# Sheet.net
KiCad netlist of a schematic drawn in Altium Designer
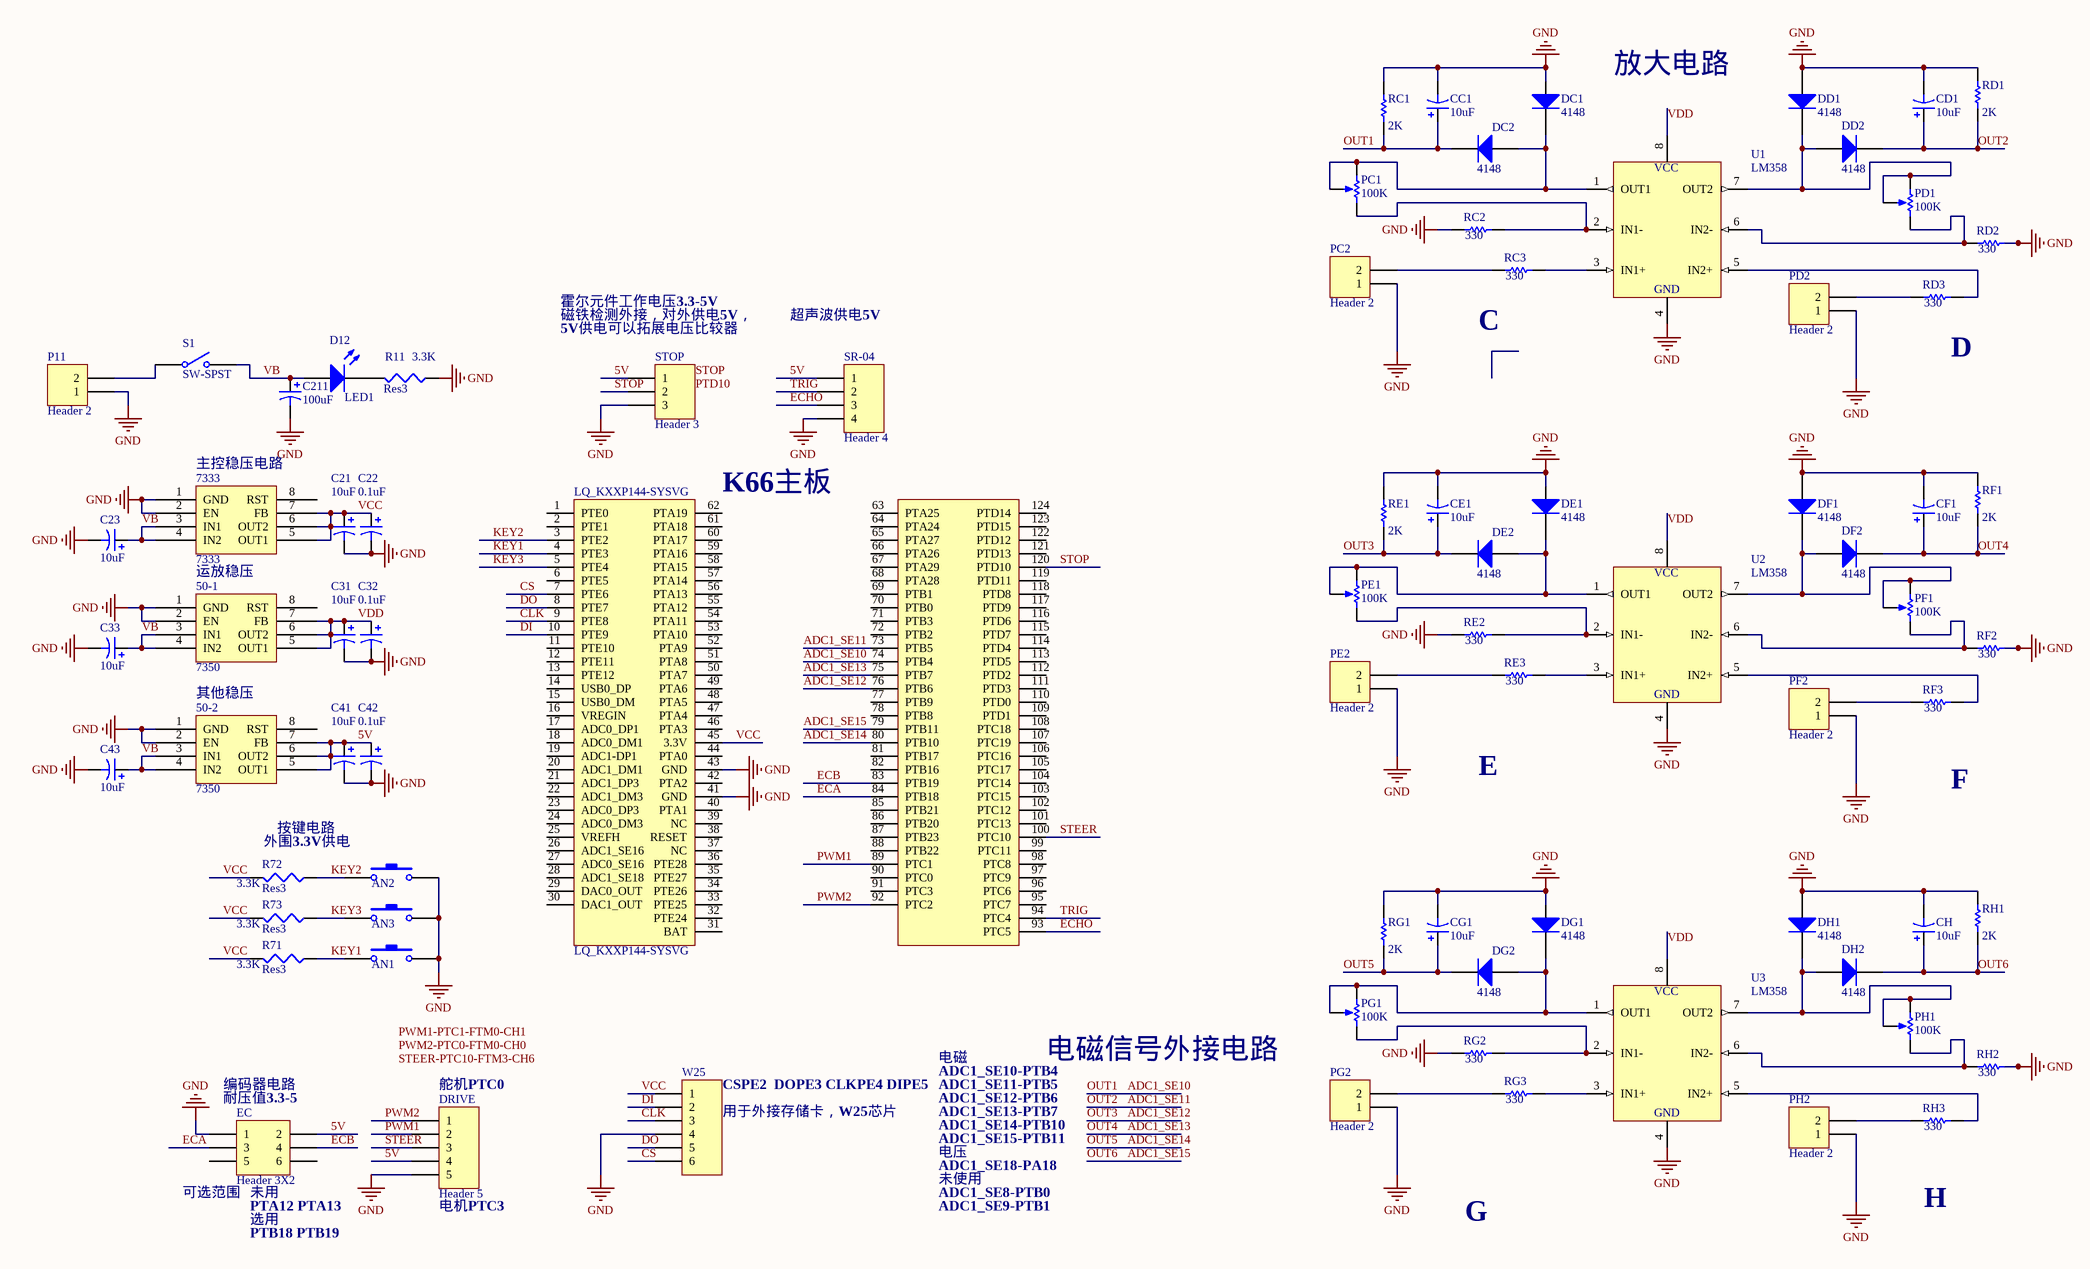
[diagram p0: Sheet.SchDoc]

(export (version "E")
  (design (tool "Eeschema 10.0.6"))
  (components
    (comp (ref "50-1") (value "7350") (footprint "SOP8_N") (libsource (lib "vehicle") (part "7350")))
    (comp (ref "50-2") (value "7350") (footprint "SOP8_N") (libsource (lib "vehicle") (part "7350")))
    (comp (ref "7333") (value "7333") (footprint "SO8_N") (libsource (lib "vehicle") (part "7333")))
    (comp (ref "AN1")
      (value "Button")
      (footprint "SMT4*6*2.5")
      (fields (field (name "PUBLISHER") "Altium Limited"))
      (libsource (lib "开关按键器件") (part "Button"))
    )
    (comp (ref "AN2")
      (value "Button")
      (footprint "SMT4*6*2.5")
      (fields (field (name "PUBLISHER") "Altium Limited"))
      (libsource (lib "开关按键器件") (part "Button"))
    )
    (comp (ref "AN3")
      (value "Button")
      (footprint "SMT4*6*2.5")
      (fields (field (name "PUBLISHER") "Altium Limited"))
      (libsource (lib "开关按键器件") (part "Button"))
    )
    (comp (ref "C21")
      (value "10uF")
      (footprint "C6032")
      (description "Polarized Capacitor (Surface Mount)")
      (fields (field (name "Comment") "Cap Pol3") (field (name "PUBLISHER") "Altium Limited"))
      (libsource (lib "Miscellaneous Devices") (part "Cap Pol3"))
    )
    (comp (ref "C22")
      (value "0.1uF")
      (footprint "C3216")
      (description "Polarized Capacitor (Surface Mount)")
      (fields (field (name "Comment") "Cap Pol3") (field (name "PUBLISHER") "Altium Limited"))
      (libsource (lib "Miscellaneous Devices") (part "Cap Pol3"))
    )
    (comp (ref "C23")
      (value "10uF")
      (footprint "C6032")
      (description "Polarized Capacitor (Surface Mount)")
      (fields (field (name "Comment") "Cap Pol3") (field (name "PUBLISHER") "Altium Limited"))
      (libsource (lib "Miscellaneous Devices") (part "Cap Pol3"))
    )
    (comp (ref "C31")
      (value "10uF")
      (footprint "C6032")
      (description "Polarized Capacitor (Surface Mount)")
      (fields (field (name "Comment") "Cap Pol3") (field (name "PUBLISHER") "Altium Limited"))
      (libsource (lib "Miscellaneous Devices") (part "Cap Pol3"))
    )
    (comp (ref "C32")
      (value "0.1uF")
      (footprint "C3216")
      (description "Polarized Capacitor (Surface Mount)")
      (fields (field (name "Comment") "Cap Pol3") (field (name "PUBLISHER") "Altium Limited"))
      (libsource (lib "Miscellaneous Devices") (part "Cap Pol3"))
    )
    (comp (ref "C33")
      (value "10uF")
      (footprint "C6032")
      (description "Polarized Capacitor (Surface Mount)")
      (fields (field (name "Comment") "Cap Pol3") (field (name "PUBLISHER") "Altium Limited"))
      (libsource (lib "Miscellaneous Devices") (part "Cap Pol3"))
    )
    (comp (ref "C41")
      (value "10uF")
      (footprint "C6032")
      (description "Polarized Capacitor (Surface Mount)")
      (fields (field (name "Comment") "Cap Pol3") (field (name "PUBLISHER") "Altium Limited"))
      (libsource (lib "Miscellaneous Devices") (part "Cap Pol3"))
    )
    (comp (ref "C42")
      (value "0.1uF")
      (footprint "C3216")
      (description "Polarized Capacitor (Surface Mount)")
      (fields (field (name "Comment") "Cap Pol3") (field (name "PUBLISHER") "Altium Limited"))
      (libsource (lib "Miscellaneous Devices") (part "Cap Pol3"))
    )
    (comp (ref "C43")
      (value "10uF")
      (footprint "C6032")
      (description "Polarized Capacitor (Surface Mount)")
      (fields (field (name "Comment") "Cap Pol3") (field (name "PUBLISHER") "Altium Limited"))
      (libsource (lib "Miscellaneous Devices") (part "Cap Pol3"))
    )
    (comp (ref "C211")
      (value "100uF")
      (footprint "C7343")
      (description "Polarized Capacitor (Surface Mount)")
      (fields (field (name "Comment") "Cap Pol3") (field (name "PUBLISHER") "Altium Limited"))
      (libsource (lib "Miscellaneous Devices") (part "Cap Pol3"))
    )
    (comp (ref "CC1")
      (value "10uF")
      (footprint "C6032")
      (description "Polarized Capacitor (Surface Mount)")
      (fields (field (name "Comment") "Cap Pol3") (field (name "PUBLISHER") "Altium Limited"))
      (libsource (lib "Miscellaneous Devices") (part "Cap Pol3"))
    )
    (comp (ref "CD1")
      (value "10uF")
      (footprint "C6032")
      (description "Polarized Capacitor (Surface Mount)")
      (fields (field (name "Comment") "Cap Pol3") (field (name "PUBLISHER") "Altium Limited"))
      (libsource (lib "Miscellaneous Devices") (part "Cap Pol3"))
    )
    (comp (ref "CE1")
      (value "10uF")
      (footprint "C6032")
      (description "Polarized Capacitor (Surface Mount)")
      (fields (field (name "Comment") "Cap Pol3") (field (name "PUBLISHER") "Altium Limited"))
      (libsource (lib "Miscellaneous Devices") (part "Cap Pol3"))
    )
    (comp (ref "CF1")
      (value "10uF")
      (footprint "C6032")
      (description "Polarized Capacitor (Surface Mount)")
      (fields (field (name "Comment") "Cap Pol3") (field (name "PUBLISHER") "Altium Limited"))
      (libsource (lib "Miscellaneous Devices") (part "Cap Pol3"))
    )
    (comp (ref "CG1")
      (value "10uF")
      (footprint "C6032")
      (description "Polarized Capacitor (Surface Mount)")
      (fields (field (name "Comment") "Cap Pol3") (field (name "PUBLISHER") "Altium Limited"))
      (libsource (lib "Miscellaneous Devices") (part "Cap Pol3"))
    )
    (comp (ref "CH")
      (value "10uF")
      (footprint "C6032")
      (description "Polarized Capacitor (Surface Mount)")
      (fields (field (name "Comment") "Cap Pol3") (field (name "PUBLISHER") "Altium Limited"))
      (libsource (lib "Miscellaneous Devices") (part "Cap Pol3"))
    )
    (comp (ref "D12")
      (value "LED1")
      (footprint "SMA")
      (description "Typical BLUE SiC LED")
      (fields (field (name "PUBLISHER") "Altium Limited"))
      (libsource (lib "Miscellaneous Devices") (part "LED3"))
    )
    (comp (ref "DC1")
      (value "4148")
      (footprint "SMA")
      (description "Default Diode")
      (fields (field (name "PUBLISHER") "Altium Limited"))
      (libsource (lib "Miscellaneous Devices") (part "Diode"))
    )
    (comp (ref "DC2")
      (value "4148")
      (footprint "SMA")
      (description "Default Diode")
      (fields (field (name "PUBLISHER") "Altium Limited"))
      (libsource (lib "Miscellaneous Devices") (part "Diode"))
    )
    (comp (ref "DD1")
      (value "4148")
      (footprint "SMA")
      (description "Default Diode")
      (fields (field (name "PUBLISHER") "Altium Limited"))
      (libsource (lib "Miscellaneous Devices") (part "Diode"))
    )
    (comp (ref "DD2")
      (value "4148")
      (footprint "SMA")
      (description "Default Diode")
      (fields (field (name "PUBLISHER") "Altium Limited"))
      (libsource (lib "Miscellaneous Devices") (part "Diode"))
    )
    (comp (ref "DE1")
      (value "4148")
      (footprint "SMA")
      (description "Default Diode")
      (fields (field (name "PUBLISHER") "Altium Limited"))
      (libsource (lib "Miscellaneous Devices") (part "Diode"))
    )
    (comp (ref "DE2")
      (value "4148")
      (footprint "SMA")
      (description "Default Diode")
      (fields (field (name "PUBLISHER") "Altium Limited"))
      (libsource (lib "Miscellaneous Devices") (part "Diode"))
    )
    (comp (ref "DF1")
      (value "4148")
      (footprint "SMA")
      (description "Default Diode")
      (fields (field (name "PUBLISHER") "Altium Limited"))
      (libsource (lib "Miscellaneous Devices") (part "Diode"))
    )
    (comp (ref "DF2")
      (value "4148")
      (footprint "SMA")
      (description "Default Diode")
      (fields (field (name "PUBLISHER") "Altium Limited"))
      (libsource (lib "Miscellaneous Devices") (part "Diode"))
    )
    (comp (ref "DG1")
      (value "4148")
      (footprint "SMA")
      (description "Default Diode")
      (fields (field (name "PUBLISHER") "Altium Limited"))
      (libsource (lib "Miscellaneous Devices") (part "Diode"))
    )
    (comp (ref "DG2")
      (value "4148")
      (footprint "SMA")
      (description "Default Diode")
      (fields (field (name "PUBLISHER") "Altium Limited"))
      (libsource (lib "Miscellaneous Devices") (part "Diode"))
    )
    (comp (ref "DH1")
      (value "4148")
      (footprint "SMA")
      (description "Default Diode")
      (fields (field (name "PUBLISHER") "Altium Limited"))
      (libsource (lib "Miscellaneous Devices") (part "Diode"))
    )
    (comp (ref "DH2")
      (value "4148")
      (footprint "SMA")
      (description "Default Diode")
      (fields (field (name "PUBLISHER") "Altium Limited"))
      (libsource (lib "Miscellaneous Devices") (part "Diode"))
    )
    (comp (ref "DRIVE")
      (value "Header 5")
      (footprint "HX2.54-5")
      (description "Header, 5-Pin")
      (fields (field (name "PUBLISHER") "Altium Limited"))
      (libsource (lib "连接器") (part "Header 5"))
    )
    (comp (ref "EC")
      (value "Header 3X2")
      (footprint "HDR2X3")
      (description "Header, 3-Pin, Dual row")
      (fields (field (name "PUBLISHER") "Altium Limited"))
      (libsource (lib "连接器") (part "Header 3X2"))
    )
    (comp (ref "LQ_KXXP144-SYSVG")
      (value "LQ_KXXP144-SYSVG")
      (footprint "LQ_KXXP144-SYSVG")
      (libsource (lib "LQ_KXXP144-SYSVGSCH") (part "LQ_KXXP144-SYSVG"))
    )
    (comp (ref "P11")
      (value "Header 2")
      (footprint "2PIN-5.08B")
      (description "Header, 2-Pin")
      (fields (field (name "PUBLISHER") "Altium Limited"))
      (libsource (lib "Miscellaneous Connectors") (part "Header 2"))
    )
    (comp (ref "PC1")
      (value "100K")
      (footprint "VR_B1")
      (description "精密可调电阻")
      (fields (field (name "Comment") "RPot") (field (name "PUBLISHER") "Altium Limited"))
      (libsource (lib "32mini") (part "RPot"))
    )
    (comp (ref "PC2")
      (value "Header 2")
      (footprint "HX2.54-2")
      (description "Header, 2-Pin")
      (fields (field (name "PUBLISHER") "Altium Limited"))
      (libsource (lib "Miscellaneous Connectors") (part "Header 2"))
    )
    (comp (ref "PD1")
      (value "100K")
      (footprint "VR_B1")
      (description "精密可调电阻")
      (fields (field (name "Comment") "RPot") (field (name "PUBLISHER") "Altium Limited"))
      (libsource (lib "32mini") (part "RPot"))
    )
    (comp (ref "PD2")
      (value "Header 2")
      (footprint "HX2.54-2")
      (description "Header, 2-Pin")
      (fields (field (name "PUBLISHER") "Altium Limited"))
      (libsource (lib "Miscellaneous Connectors") (part "Header 2"))
    )
    (comp (ref "PE1")
      (value "100K")
      (footprint "VR_B1")
      (description "精密可调电阻")
      (fields (field (name "Comment") "RPot") (field (name "PUBLISHER") "Altium Limited"))
      (libsource (lib "32mini") (part "RPot"))
    )
    (comp (ref "PE2")
      (value "Header 2")
      (footprint "HX2.54-2")
      (description "Header, 2-Pin")
      (fields (field (name "PUBLISHER") "Altium Limited"))
      (libsource (lib "Miscellaneous Connectors") (part "Header 2"))
    )
    (comp (ref "PF1")
      (value "100K")
      (footprint "VR_B1")
      (description "精密可调电阻")
      (fields (field (name "Comment") "RPot") (field (name "PUBLISHER") "Altium Limited"))
      (libsource (lib "32mini") (part "RPot"))
    )
    (comp (ref "PF2")
      (value "Header 2")
      (footprint "HX2.54-2")
      (description "Header, 2-Pin")
      (fields (field (name "PUBLISHER") "Altium Limited"))
      (libsource (lib "Miscellaneous Connectors") (part "Header 2"))
    )
    (comp (ref "PG1")
      (value "100K")
      (footprint "VR_B1")
      (description "精密可调电阻")
      (fields (field (name "Comment") "RPot") (field (name "PUBLISHER") "Altium Limited"))
      (libsource (lib "32mini") (part "RPot"))
    )
    (comp (ref "PG2")
      (value "Header 2")
      (footprint "HX2.54-2")
      (description "Header, 2-Pin")
      (fields (field (name "PUBLISHER") "Altium Limited"))
      (libsource (lib "Miscellaneous Connectors") (part "Header 2"))
    )
    (comp (ref "PH1")
      (value "100K")
      (footprint "VR_B1")
      (description "精密可调电阻")
      (fields (field (name "Comment") "RPot") (field (name "PUBLISHER") "Altium Limited"))
      (libsource (lib "32mini") (part "RPot"))
    )
    (comp (ref "PH2")
      (value "Header 2")
      (footprint "HX2.54-2")
      (description "Header, 2-Pin")
      (fields (field (name "PUBLISHER") "Altium Limited"))
      (libsource (lib "Miscellaneous Connectors") (part "Header 2"))
    )
    (comp (ref "R11")
      (value "Res3")
      (footprint "R0805")
      (description "Resistor")
      (fields (field (name "ALTIUM_VALUE") "3.3K") (field (name "PUBLISHER") "Altium Limited"))
      (libsource (lib "Miscellaneous Devices") (part "Res3"))
    )
    (comp (ref "R71")
      (value "Res3")
      (footprint "R0805")
      (description "Resistor")
      (fields (field (name "ALTIUM_VALUE") "3.3K") (field (name "PUBLISHER") "Altium Limited"))
      (libsource (lib "Miscellaneous Devices") (part "Res3"))
    )
    (comp (ref "R72")
      (value "Res3")
      (footprint "R0805")
      (description "Resistor")
      (fields (field (name "ALTIUM_VALUE") "3.3K") (field (name "PUBLISHER") "Altium Limited"))
      (libsource (lib "Miscellaneous Devices") (part "Res3"))
    )
    (comp (ref "R73")
      (value "Res3")
      (footprint "R0805")
      (description "Resistor")
      (fields (field (name "ALTIUM_VALUE") "3.3K") (field (name "PUBLISHER") "Altium Limited"))
      (libsource (lib "Miscellaneous Devices") (part "Res3"))
    )
    (comp (ref "RC1")
      (value "2K")
      (footprint "C0805")
      (description "Semiconductor Resistor")
      (fields (field (name "Comment") "Res Semi") (field (name "PUBLISHER") "Altium Limited"))
      (libsource (lib "Miscellaneous Devices") (part "Res Semi"))
    )
    (comp (ref "RC2")
      (value "330")
      (footprint "C0805")
      (description "Semiconductor Resistor")
      (fields (field (name "Comment") "Res Semi") (field (name "PUBLISHER") "Altium Limited"))
      (libsource (lib "Miscellaneous Devices") (part "Res Semi"))
    )
    (comp (ref "RC3")
      (value "330")
      (footprint "C0805")
      (description "Semiconductor Resistor")
      (fields (field (name "Comment") "Res Semi") (field (name "PUBLISHER") "Altium Limited"))
      (libsource (lib "Miscellaneous Devices") (part "Res Semi"))
    )
    (comp (ref "RD1")
      (value "2K")
      (footprint "C0805")
      (description "Semiconductor Resistor")
      (fields (field (name "Comment") "Res Semi") (field (name "PUBLISHER") "Altium Limited"))
      (libsource (lib "Miscellaneous Devices") (part "Res Semi"))
    )
    (comp (ref "RD2")
      (value "330")
      (footprint "C0805")
      (description "Semiconductor Resistor")
      (fields (field (name "Comment") "Res Semi") (field (name "PUBLISHER") "Altium Limited"))
      (libsource (lib "Miscellaneous Devices") (part "Res Semi"))
    )
    (comp (ref "RD3")
      (value "330")
      (footprint "C0805")
      (description "Semiconductor Resistor")
      (fields (field (name "Comment") "Res Semi") (field (name "PUBLISHER") "Altium Limited"))
      (libsource (lib "Miscellaneous Devices") (part "Res Semi"))
    )
    (comp (ref "RE1")
      (value "2K")
      (footprint "C0805")
      (description "Semiconductor Resistor")
      (fields (field (name "Comment") "Res Semi") (field (name "PUBLISHER") "Altium Limited"))
      (libsource (lib "Miscellaneous Devices") (part "Res Semi"))
    )
    (comp (ref "RE2")
      (value "330")
      (footprint "C0805")
      (description "Semiconductor Resistor")
      (fields (field (name "Comment") "Res Semi") (field (name "PUBLISHER") "Altium Limited"))
      (libsource (lib "Miscellaneous Devices") (part "Res Semi"))
    )
    (comp (ref "RE3")
      (value "330")
      (footprint "C0805")
      (description "Semiconductor Resistor")
      (fields (field (name "Comment") "Res Semi") (field (name "PUBLISHER") "Altium Limited"))
      (libsource (lib "Miscellaneous Devices") (part "Res Semi"))
    )
    (comp (ref "RF1")
      (value "2K")
      (footprint "C0805")
      (description "Semiconductor Resistor")
      (fields (field (name "Comment") "Res Semi") (field (name "PUBLISHER") "Altium Limited"))
      (libsource (lib "Miscellaneous Devices") (part "Res Semi"))
    )
    (comp (ref "RF2")
      (value "330")
      (footprint "C0805")
      (description "Semiconductor Resistor")
      (fields (field (name "Comment") "Res Semi") (field (name "PUBLISHER") "Altium Limited"))
      (libsource (lib "Miscellaneous Devices") (part "Res Semi"))
    )
    (comp (ref "RF3")
      (value "330")
      (footprint "C0805")
      (description "Semiconductor Resistor")
      (fields (field (name "Comment") "Res Semi") (field (name "PUBLISHER") "Altium Limited"))
      (libsource (lib "Miscellaneous Devices") (part "Res Semi"))
    )
    (comp (ref "RG1")
      (value "2K")
      (footprint "C0805")
      (description "Semiconductor Resistor")
      (fields (field (name "Comment") "Res Semi") (field (name "PUBLISHER") "Altium Limited"))
      (libsource (lib "Miscellaneous Devices") (part "Res Semi"))
    )
    (comp (ref "RG2")
      (value "330")
      (footprint "C0805")
      (description "Semiconductor Resistor")
      (fields (field (name "Comment") "Res Semi") (field (name "PUBLISHER") "Altium Limited"))
      (libsource (lib "Miscellaneous Devices") (part "Res Semi"))
    )
    (comp (ref "RG3")
      (value "330")
      (footprint "C0805")
      (description "Semiconductor Resistor")
      (fields (field (name "Comment") "Res Semi") (field (name "PUBLISHER") "Altium Limited"))
      (libsource (lib "Miscellaneous Devices") (part "Res Semi"))
    )
    (comp (ref "RH1")
      (value "2K")
      (footprint "C0805")
      (description "Semiconductor Resistor")
      (fields (field (name "Comment") "Res Semi") (field (name "PUBLISHER") "Altium Limited"))
      (libsource (lib "Miscellaneous Devices") (part "Res Semi"))
    )
    (comp (ref "RH2")
      (value "330")
      (footprint "C0805")
      (description "Semiconductor Resistor")
      (fields (field (name "Comment") "Res Semi") (field (name "PUBLISHER") "Altium Limited"))
      (libsource (lib "Miscellaneous Devices") (part "Res Semi"))
    )
    (comp (ref "RH3")
      (value "330")
      (footprint "C0805")
      (description "Semiconductor Resistor")
      (fields (field (name "Comment") "Res Semi") (field (name "PUBLISHER") "Altium Limited"))
      (libsource (lib "Miscellaneous Devices") (part "Res Semi"))
    )
    (comp (ref "S1")
      (value "SW-SPST")
      (footprint "SW-TO3")
      (description "Single-Pole, Single-Throw Switch")
      (fields (field (name "PUBLISHER") "Altium Limited"))
      (libsource (lib "开关按键器件") (part "SW-SPST"))
    )
    (comp (ref "SR-04")
      (value "Header 4")
      (footprint "HX2.54-4")
      (description "Header, 4-Pin")
      (fields (field (name "PUBLISHER") "Altium Limited"))
      (libsource (lib "连接器") (part "Header 4"))
    )
    (comp (ref "STOP")
      (value "Header 3")
      (footprint "HX2.54-3")
      (description "Header, 3-Pin")
      (fields (field (name "PUBLISHER") "Altium Limited"))
      (libsource (lib "连接器") (part "Header 3"))
    )
    (comp (ref "U1") (value "LM358") (footprint "SOP8_M") (libsource (lib "Schlib1") (part "LM358")))
    (comp (ref "U2") (value "LM358") (footprint "SOP8_M") (libsource (lib "Schlib1") (part "LM358")))
    (comp (ref "U3") (value "LM358") (footprint "SOP8_M") (libsource (lib "Schlib1") (part "LM358")))
    (comp (ref "W25")
      (value "MHDR1X6")
      (footprint "HDR1X6")
      (description "Header, 6-Pin")
      (fields (field (name "PUBLISHER") "Altium Limited"))
      (libsource (lib "连接器") (part "MHDR1X6"))
    )
  )
  (nets
    (net (code "1") (name "/5V") (class "Default")
      (node (ref "50-2") (pin "5") (pinfunction "OUT1_5") (pintype "passive"))
      (node (ref "50-2") (pin "6") (pinfunction "OUT2_6") (pintype "passive"))
      (node (ref "50-2") (pin "7") (pinfunction "FB_7") (pintype "passive"))
      (node (ref "C41") (pin "1") (pinfunction "1_1") (pintype "passive"))
      (node (ref "C42") (pin "1") (pinfunction "1_1") (pintype "passive"))
      (node (ref "DRIVE") (pin "4") (pinfunction "4_4") (pintype "passive"))
      (node (ref "EC") (pin "2") (pinfunction "2_2") (pintype "passive"))
      (node (ref "SR-04") (pin "1") (pinfunction "1_1") (pintype "passive"))
      (node (ref "STOP") (pin "1") (pinfunction "1_1") (pintype "passive"))
    )
    (net (code "2") (name "/ADC1_SE10") (class "Default")
      (node (ref "CC1") (pin "1") (pinfunction "1_1") (pintype "passive"))
      (node (ref "DC2") (pin "2") (pinfunction "K_2") (pintype "passive"))
      (node (ref "LQ_KXXP144-SYSVG") (pin "74") (pinfunction "PTB4_74") (pintype "passive"))
      (node (ref "RC1") (pin "1") (pinfunction "1_1") (pintype "passive"))
    )
    (net (code "3") (name "/ADC1_SE11") (class "Default")
      (node (ref "CD1") (pin "1") (pinfunction "1_1") (pintype "passive"))
      (node (ref "DD2") (pin "2") (pinfunction "K_2") (pintype "passive"))
      (node (ref "LQ_KXXP144-SYSVG") (pin "73") (pinfunction "PTB5_73") (pintype "passive"))
      (node (ref "RD1") (pin "1") (pinfunction "1_1") (pintype "passive"))
    )
    (net (code "4") (name "/ADC1_SE12") (class "Default")
      (node (ref "CE1") (pin "1") (pinfunction "1_1") (pintype "passive"))
      (node (ref "DE2") (pin "2") (pinfunction "K_2") (pintype "passive"))
      (node (ref "LQ_KXXP144-SYSVG") (pin "76") (pinfunction "PTB6_76") (pintype "passive"))
      (node (ref "RE1") (pin "1") (pinfunction "1_1") (pintype "passive"))
    )
    (net (code "5") (name "/ADC1_SE13") (class "Default")
      (node (ref "CF1") (pin "1") (pinfunction "1_1") (pintype "passive"))
      (node (ref "DF2") (pin "2") (pinfunction "K_2") (pintype "passive"))
      (node (ref "LQ_KXXP144-SYSVG") (pin "75") (pinfunction "PTB7_75") (pintype "passive"))
      (node (ref "RF1") (pin "1") (pinfunction "1_1") (pintype "passive"))
    )
    (net (code "6") (name "/ADC1_SE14") (class "Default")
      (node (ref "CG1") (pin "1") (pinfunction "1_1") (pintype "passive"))
      (node (ref "DG2") (pin "2") (pinfunction "K_2") (pintype "passive"))
      (node (ref "LQ_KXXP144-SYSVG") (pin "80") (pinfunction "PTB10_80") (pintype "passive"))
      (node (ref "RG1") (pin "1") (pinfunction "1_1") (pintype "passive"))
    )
    (net (code "7") (name "/ADC1_SE15") (class "Default")
      (node (ref "CH") (pin "1") (pinfunction "1_1") (pintype "passive"))
      (node (ref "DH2") (pin "2") (pinfunction "K_2") (pintype "passive"))
      (node (ref "LQ_KXXP144-SYSVG") (pin "79") (pinfunction "PTB11_79") (pintype "passive"))
      (node (ref "RH1") (pin "1") (pinfunction "1_1") (pintype "passive"))
    )
    (net (code "8") (name "/CLK") (class "Default")
      (node (ref "LQ_KXXP144-SYSVG") (pin "9") (pinfunction "PTE8_9") (pintype "passive"))
      (node (ref "W25") (pin "3") (pinfunction "3_3") (pintype "passive"))
    )
    (net (code "9") (name "/CS") (class "Default")
      (node (ref "LQ_KXXP144-SYSVG") (pin "7") (pinfunction "PTE6_7") (pintype "passive"))
      (node (ref "W25") (pin "6") (pinfunction "6_6") (pintype "passive"))
    )
    (net (code "10") (name "/DI") (class "Default")
      (node (ref "LQ_KXXP144-SYSVG") (pin "10") (pinfunction "PTE9_10") (pintype "passive"))
      (node (ref "W25") (pin "2") (pinfunction "2_2") (pintype "passive"))
    )
    (net (code "11") (name "/DO") (class "Default")
      (node (ref "LQ_KXXP144-SYSVG") (pin "8") (pinfunction "PTE7_8") (pintype "passive"))
      (node (ref "W25") (pin "5") (pinfunction "5_5") (pintype "passive"))
    )
    (net (code "12") (name "/ECA") (class "Default")
      (node (ref "EC") (pin "3") (pinfunction "3_3") (pintype "passive"))
      (node (ref "LQ_KXXP144-SYSVG") (pin "84") (pinfunction "PTB18_84") (pintype "passive"))
    )
    (net (code "13") (name "/ECB") (class "Default")
      (node (ref "EC") (pin "4") (pinfunction "4_4") (pintype "passive"))
      (node (ref "LQ_KXXP144-SYSVG") (pin "83") (pinfunction "PTB19_83") (pintype "passive"))
    )
    (net (code "14") (name "/ECHO") (class "Default")
      (node (ref "LQ_KXXP144-SYSVG") (pin "93") (pinfunction "PTC5_93") (pintype "passive"))
      (node (ref "SR-04") (pin "3") (pinfunction "3_3") (pintype "passive"))
    )
    (net (code "15") (name "/KEY1") (class "Default")
      (node (ref "AN1") (pin "2") (pinfunction "2_2") (pintype "passive"))
      (node (ref "LQ_KXXP144-SYSVG") (pin "4") (pinfunction "PTE3_4") (pintype "passive"))
      (node (ref "R71") (pin "1") (pinfunction "1_1") (pintype "passive"))
    )
    (net (code "16") (name "/KEY2") (class "Default")
      (node (ref "AN2") (pin "2") (pinfunction "2_2") (pintype "passive"))
      (node (ref "LQ_KXXP144-SYSVG") (pin "3") (pinfunction "PTE2_3") (pintype "passive"))
      (node (ref "R72") (pin "1") (pinfunction "1_1") (pintype "passive"))
    )
    (net (code "17") (name "/KEY3") (class "Default")
      (node (ref "AN3") (pin "2") (pinfunction "2_2") (pintype "passive"))
      (node (ref "LQ_KXXP144-SYSVG") (pin "5") (pinfunction "PTE4_5") (pintype "passive"))
      (node (ref "R73") (pin "1") (pinfunction "1_1") (pintype "passive"))
    )
    (net (code "19") (name "/PWM1") (class "Default")
      (node (ref "DRIVE") (pin "2") (pinfunction "2_2") (pintype "passive"))
      (node (ref "LQ_KXXP144-SYSVG") (pin "89") (pinfunction "PTC1_89") (pintype "passive"))
    )
    (net (code "21") (name "/PWM2") (class "Default")
      (node (ref "DRIVE") (pin "1") (pinfunction "1_1") (pintype "passive"))
      (node (ref "LQ_KXXP144-SYSVG") (pin "92") (pinfunction "PTC2_92") (pintype "passive"))
    )
    (net (code "23") (name "/STEER") (class "Default")
      (node (ref "DRIVE") (pin "3") (pinfunction "3_3") (pintype "passive"))
      (node (ref "LQ_KXXP144-SYSVG") (pin "100") (pinfunction "PTC10_100") (pintype "passive"))
    )
    (net (code "25") (name "/STOP") (class "Default")
      (node (ref "LQ_KXXP144-SYSVG") (pin "120") (pinfunction "PTD10_120") (pintype "passive"))
      (node (ref "STOP") (pin "2") (pinfunction "2_2") (pintype "passive"))
    )
    (net (code "26") (name "/TRIG") (class "Default")
      (node (ref "LQ_KXXP144-SYSVG") (pin "94") (pinfunction "PTC4_94") (pintype "passive"))
      (node (ref "SR-04") (pin "2") (pinfunction "2_2") (pintype "passive"))
    )
    (net (code "27") (name "/VB") (class "Default")
      (node (ref "50-1") (pin "3") (pinfunction "IN1_3") (pintype "passive"))
      (node (ref "50-1") (pin "4") (pinfunction "IN2_4") (pintype "passive"))
      (node (ref "50-2") (pin "3") (pinfunction "IN1_3") (pintype "passive"))
      (node (ref "50-2") (pin "4") (pinfunction "IN2_4") (pintype "passive"))
      (node (ref "7333") (pin "3") (pinfunction "IN1_3") (pintype "passive"))
      (node (ref "7333") (pin "4") (pinfunction "IN2_4") (pintype "passive"))
      (node (ref "C211") (pin "1") (pinfunction "1_1") (pintype "passive"))
      (node (ref "C23") (pin "1") (pinfunction "1_1") (pintype "passive"))
      (node (ref "C33") (pin "1") (pinfunction "1_1") (pintype "passive"))
      (node (ref "C43") (pin "1") (pinfunction "1_1") (pintype "passive"))
      (node (ref "D12") (pin "1") (pinfunction "A_1") (pintype "passive"))
      (node (ref "S1") (pin "2") (pinfunction "NO_2") (pintype "passive"))
    )
    (net (code "28") (name "/VCC") (class "Default")
      (node (ref "7333") (pin "5") (pinfunction "OUT1_5") (pintype "passive"))
      (node (ref "7333") (pin "6") (pinfunction "OUT2_6") (pintype "passive"))
      (node (ref "7333") (pin "7") (pinfunction "FB_7") (pintype "passive"))
      (node (ref "C21") (pin "1") (pinfunction "1_1") (pintype "passive"))
      (node (ref "C22") (pin "1") (pinfunction "1_1") (pintype "passive"))
      (node (ref "LQ_KXXP144-SYSVG") (pin "45") (pinfunction "3.3V_45") (pintype "passive"))
      (node (ref "R71") (pin "2") (pinfunction "2_2") (pintype "passive"))
      (node (ref "R72") (pin "2") (pinfunction "2_2") (pintype "passive"))
      (node (ref "R73") (pin "2") (pinfunction "2_2") (pintype "passive"))
      (node (ref "W25") (pin "1") (pinfunction "1_1") (pintype "passive"))
    )
    (net (code "29") (name "/VDD") (class "Default")
      (node (ref "50-1") (pin "5") (pinfunction "OUT1_5") (pintype "passive"))
      (node (ref "50-1") (pin "6") (pinfunction "OUT2_6") (pintype "passive"))
      (node (ref "50-1") (pin "7") (pinfunction "FB_7") (pintype "passive"))
      (node (ref "C31") (pin "1") (pinfunction "1_1") (pintype "passive"))
      (node (ref "C32") (pin "1") (pinfunction "1_1") (pintype "passive"))
      (node (ref "U1") (pin "8") (pinfunction "VCC_8") (pintype "power_in"))
      (node (ref "U2") (pin "8") (pinfunction "VCC_8") (pintype "power_in"))
      (node (ref "U3") (pin "8") (pinfunction "VCC_8") (pintype "power_in"))
    )
    (net (code "30") (name "GND") (class "Default")
      (node (ref "50-1") (pin "1") (pinfunction "GND_1") (pintype "passive"))
      (node (ref "50-1") (pin "2") (pinfunction "EN_2") (pintype "passive"))
      (node (ref "50-2") (pin "1") (pinfunction "GND_1") (pintype "passive"))
      (node (ref "50-2") (pin "2") (pinfunction "EN_2") (pintype "passive"))
      (node (ref "7333") (pin "1") (pinfunction "GND_1") (pintype "passive"))
      (node (ref "7333") (pin "2") (pinfunction "EN_2") (pintype "passive"))
      (node (ref "AN1") (pin "1") (pinfunction "1_1") (pintype "passive"))
      (node (ref "AN2") (pin "1") (pinfunction "1_1") (pintype "passive"))
      (node (ref "AN3") (pin "1") (pinfunction "1_1") (pintype "passive"))
      (node (ref "C21") (pin "2") (pinfunction "2_2") (pintype "passive"))
      (node (ref "C211") (pin "2") (pinfunction "2_2") (pintype "passive"))
      (node (ref "C22") (pin "2") (pinfunction "2_2") (pintype "passive"))
      (node (ref "C23") (pin "2") (pinfunction "2_2") (pintype "passive"))
      (node (ref "C31") (pin "2") (pinfunction "2_2") (pintype "passive"))
      (node (ref "C32") (pin "2") (pinfunction "2_2") (pintype "passive"))
      (node (ref "C33") (pin "2") (pinfunction "2_2") (pintype "passive"))
      (node (ref "C41") (pin "2") (pinfunction "2_2") (pintype "passive"))
      (node (ref "C42") (pin "2") (pinfunction "2_2") (pintype "passive"))
      (node (ref "C43") (pin "2") (pinfunction "2_2") (pintype "passive"))
      (node (ref "CC1") (pin "2") (pinfunction "2_2") (pintype "passive"))
      (node (ref "CD1") (pin "2") (pinfunction "2_2") (pintype "passive"))
      (node (ref "CE1") (pin "2") (pinfunction "2_2") (pintype "passive"))
      (node (ref "CF1") (pin "2") (pinfunction "2_2") (pintype "passive"))
      (node (ref "CG1") (pin "2") (pinfunction "2_2") (pintype "passive"))
      (node (ref "CH") (pin "2") (pinfunction "2_2") (pintype "passive"))
      (node (ref "DC1") (pin "1") (pinfunction "A_1") (pintype "passive"))
      (node (ref "DD1") (pin "1") (pinfunction "A_1") (pintype "passive"))
      (node (ref "DE1") (pin "1") (pinfunction "A_1") (pintype "passive"))
      (node (ref "DF1") (pin "1") (pinfunction "A_1") (pintype "passive"))
      (node (ref "DG1") (pin "1") (pinfunction "A_1") (pintype "passive"))
      (node (ref "DH1") (pin "1") (pinfunction "A_1") (pintype "passive"))
      (node (ref "DRIVE") (pin "5") (pinfunction "5_5") (pintype "passive"))
      (node (ref "EC") (pin "1") (pinfunction "1_1") (pintype "passive"))
      (node (ref "LQ_KXXP144-SYSVG") (pin "41") (pinfunction "GND_41") (pintype "passive"))
      (node (ref "LQ_KXXP144-SYSVG") (pin "43") (pinfunction "GND_43") (pintype "passive"))
      (node (ref "P11") (pin "1") (pinfunction "1_1") (pintype "passive"))
      (node (ref "PC2") (pin "1") (pinfunction "1_1") (pintype "passive"))
      (node (ref "PD2") (pin "1") (pinfunction "1_1") (pintype "passive"))
      (node (ref "PE2") (pin "1") (pinfunction "1_1") (pintype "passive"))
      (node (ref "PF2") (pin "1") (pinfunction "1_1") (pintype "passive"))
      (node (ref "PG2") (pin "1") (pinfunction "1_1") (pintype "passive"))
      (node (ref "PH2") (pin "1") (pinfunction "1_1") (pintype "passive"))
      (node (ref "R11") (pin "1") (pinfunction "1_1") (pintype "passive"))
      (node (ref "RC1") (pin "2") (pinfunction "2_2") (pintype "passive"))
      (node (ref "RC2") (pin "1") (pinfunction "1_1") (pintype "passive"))
      (node (ref "RD1") (pin "2") (pinfunction "2_2") (pintype "passive"))
      (node (ref "RD2") (pin "2") (pinfunction "2_2") (pintype "passive"))
      (node (ref "RE1") (pin "2") (pinfunction "2_2") (pintype "passive"))
      (node (ref "RE2") (pin "1") (pinfunction "1_1") (pintype "passive"))
      (node (ref "RF1") (pin "2") (pinfunction "2_2") (pintype "passive"))
      (node (ref "RF2") (pin "2") (pinfunction "2_2") (pintype "passive"))
      (node (ref "RG1") (pin "2") (pinfunction "2_2") (pintype "passive"))
      (node (ref "RG2") (pin "1") (pinfunction "1_1") (pintype "passive"))
      (node (ref "RH1") (pin "2") (pinfunction "2_2") (pintype "passive"))
      (node (ref "RH2") (pin "2") (pinfunction "2_2") (pintype "passive"))
      (node (ref "SR-04") (pin "4") (pinfunction "4_4") (pintype "passive"))
      (node (ref "STOP") (pin "3") (pinfunction "3_3") (pintype "passive"))
      (node (ref "U1") (pin "4") (pinfunction "GND_4") (pintype "passive"))
      (node (ref "U2") (pin "4") (pinfunction "GND_4") (pintype "passive"))
      (node (ref "U3") (pin "4") (pinfunction "GND_4") (pintype "passive"))
      (node (ref "W25") (pin "4") (pinfunction "4_4") (pintype "passive"))
    )
    (net (code "31") (name "Net-(D12-K)") (class "Default")
      (node (ref "D12") (pin "2") (pinfunction "K_2") (pintype "passive"))
      (node (ref "R11") (pin "2") (pinfunction "2_2") (pintype "passive"))
    )
    (net (code "32") (name "Net-(DC1-K)") (class "Default")
      (node (ref "DC1") (pin "2") (pinfunction "K_2") (pintype "passive"))
      (node (ref "DC2") (pin "1") (pinfunction "A_1") (pintype "passive"))
      (node (ref "PC1") (pin "1") (pinfunction "TOP_1") (pintype "passive"))
      (node (ref "PC1") (pin "2") (pinfunction "TAP_2") (pintype "passive"))
      (node (ref "U1") (pin "1") (pinfunction "OUT1_1") (pintype "output"))
    )
    (net (code "33") (name "Net-(DD1-K)") (class "Default")
      (node (ref "DD1") (pin "2") (pinfunction "K_2") (pintype "passive"))
      (node (ref "DD2") (pin "1") (pinfunction "A_1") (pintype "passive"))
      (node (ref "PD1") (pin "1") (pinfunction "TOP_1") (pintype "passive"))
      (node (ref "PD1") (pin "2") (pinfunction "TAP_2") (pintype "passive"))
      (node (ref "U1") (pin "7") (pinfunction "OUT2_7") (pintype "output"))
    )
    (net (code "34") (name "Net-(DE1-K)") (class "Default")
      (node (ref "DE1") (pin "2") (pinfunction "K_2") (pintype "passive"))
      (node (ref "DE2") (pin "1") (pinfunction "A_1") (pintype "passive"))
      (node (ref "PE1") (pin "1") (pinfunction "TOP_1") (pintype "passive"))
      (node (ref "PE1") (pin "2") (pinfunction "TAP_2") (pintype "passive"))
      (node (ref "U2") (pin "1") (pinfunction "OUT1_1") (pintype "output"))
    )
    (net (code "35") (name "Net-(DF1-K)") (class "Default")
      (node (ref "DF1") (pin "2") (pinfunction "K_2") (pintype "passive"))
      (node (ref "DF2") (pin "1") (pinfunction "A_1") (pintype "passive"))
      (node (ref "PF1") (pin "1") (pinfunction "TOP_1") (pintype "passive"))
      (node (ref "PF1") (pin "2") (pinfunction "TAP_2") (pintype "passive"))
      (node (ref "U2") (pin "7") (pinfunction "OUT2_7") (pintype "output"))
    )
    (net (code "36") (name "Net-(DG1-K)") (class "Default")
      (node (ref "DG1") (pin "2") (pinfunction "K_2") (pintype "passive"))
      (node (ref "DG2") (pin "1") (pinfunction "A_1") (pintype "passive"))
      (node (ref "PG1") (pin "1") (pinfunction "TOP_1") (pintype "passive"))
      (node (ref "PG1") (pin "2") (pinfunction "TAP_2") (pintype "passive"))
      (node (ref "U3") (pin "1") (pinfunction "OUT1_1") (pintype "output"))
    )
    (net (code "37") (name "Net-(DH1-K)") (class "Default")
      (node (ref "DH1") (pin "2") (pinfunction "K_2") (pintype "passive"))
      (node (ref "DH2") (pin "1") (pinfunction "A_1") (pintype "passive"))
      (node (ref "PH1") (pin "1") (pinfunction "TOP_1") (pintype "passive"))
      (node (ref "PH1") (pin "2") (pinfunction "TAP_2") (pintype "passive"))
      (node (ref "U3") (pin "7") (pinfunction "OUT2_7") (pintype "output"))
    )
    (net (code "38") (name "Net-(PC1-BOT)") (class "Default")
      (node (ref "PC1") (pin "3") (pinfunction "BOT_3") (pintype "passive"))
      (node (ref "RC2") (pin "2") (pinfunction "2_2") (pintype "passive"))
      (node (ref "U1") (pin "2") (pinfunction "IN1-_2") (pintype "input"))
    )
    (net (code "39") (name "Net-(PC2-Pad2)") (class "Default")
      (node (ref "PC2") (pin "2") (pinfunction "2_2") (pintype "passive"))
      (node (ref "RC3") (pin "1") (pinfunction "1_1") (pintype "passive"))
    )
    (net (code "40") (name "Net-(PD1-BOT)") (class "Default")
      (node (ref "PD1") (pin "3") (pinfunction "BOT_3") (pintype "passive"))
      (node (ref "RD2") (pin "1") (pinfunction "1_1") (pintype "passive"))
      (node (ref "U1") (pin "6") (pinfunction "IN2-_6") (pintype "input"))
    )
    (net (code "41") (name "Net-(PD2-Pad2)") (class "Default")
      (node (ref "PD2") (pin "2") (pinfunction "2_2") (pintype "passive"))
      (node (ref "RD3") (pin "1") (pinfunction "1_1") (pintype "passive"))
    )
    (net (code "42") (name "Net-(PE1-BOT)") (class "Default")
      (node (ref "PE1") (pin "3") (pinfunction "BOT_3") (pintype "passive"))
      (node (ref "RE2") (pin "2") (pinfunction "2_2") (pintype "passive"))
      (node (ref "U2") (pin "2") (pinfunction "IN1-_2") (pintype "input"))
    )
    (net (code "43") (name "Net-(PE2-Pad2)") (class "Default")
      (node (ref "PE2") (pin "2") (pinfunction "2_2") (pintype "passive"))
      (node (ref "RE3") (pin "1") (pinfunction "1_1") (pintype "passive"))
    )
    (net (code "44") (name "Net-(PF1-BOT)") (class "Default")
      (node (ref "PF1") (pin "3") (pinfunction "BOT_3") (pintype "passive"))
      (node (ref "RF2") (pin "1") (pinfunction "1_1") (pintype "passive"))
      (node (ref "U2") (pin "6") (pinfunction "IN2-_6") (pintype "input"))
    )
    (net (code "45") (name "Net-(PF2-Pad2)") (class "Default")
      (node (ref "PF2") (pin "2") (pinfunction "2_2") (pintype "passive"))
      (node (ref "RF3") (pin "1") (pinfunction "1_1") (pintype "passive"))
    )
    (net (code "46") (name "Net-(PG1-BOT)") (class "Default")
      (node (ref "PG1") (pin "3") (pinfunction "BOT_3") (pintype "passive"))
      (node (ref "RG2") (pin "2") (pinfunction "2_2") (pintype "passive"))
      (node (ref "U3") (pin "2") (pinfunction "IN1-_2") (pintype "input"))
    )
    (net (code "47") (name "Net-(PG2-Pad2)") (class "Default")
      (node (ref "PG2") (pin "2") (pinfunction "2_2") (pintype "passive"))
      (node (ref "RG3") (pin "1") (pinfunction "1_1") (pintype "passive"))
    )
    (net (code "48") (name "Net-(PH1-BOT)") (class "Default")
      (node (ref "PH1") (pin "3") (pinfunction "BOT_3") (pintype "passive"))
      (node (ref "RH2") (pin "1") (pinfunction "1_1") (pintype "passive"))
      (node (ref "U3") (pin "6") (pinfunction "IN2-_6") (pintype "input"))
    )
    (net (code "49") (name "Net-(PH2-Pad2)") (class "Default")
      (node (ref "PH2") (pin "2") (pinfunction "2_2") (pintype "passive"))
      (node (ref "RH3") (pin "1") (pinfunction "1_1") (pintype "passive"))
    )
    (net (code "50") (name "Net-(S1-COMMON)") (class "Default")
      (node (ref "P11") (pin "2") (pinfunction "2_2") (pintype "passive"))
      (node (ref "S1") (pin "1") (pinfunction "COMMON_1") (pintype "passive"))
    )
    (net (code "51") (name "Net-(U1-IN1+)") (class "Default")
      (node (ref "RC3") (pin "2") (pinfunction "2_2") (pintype "passive"))
      (node (ref "U1") (pin "3") (pinfunction "IN1+_3") (pintype "input"))
    )
    (net (code "52") (name "Net-(U1-IN2+)") (class "Default")
      (node (ref "RD3") (pin "2") (pinfunction "2_2") (pintype "passive"))
      (node (ref "U1") (pin "5") (pinfunction "IN2+_5") (pintype "input"))
    )
    (net (code "53") (name "Net-(U2-IN1+)") (class "Default")
      (node (ref "RE3") (pin "2") (pinfunction "2_2") (pintype "passive"))
      (node (ref "U2") (pin "3") (pinfunction "IN1+_3") (pintype "input"))
    )
    (net (code "54") (name "Net-(U2-IN2+)") (class "Default")
      (node (ref "RF3") (pin "2") (pinfunction "2_2") (pintype "passive"))
      (node (ref "U2") (pin "5") (pinfunction "IN2+_5") (pintype "input"))
    )
    (net (code "55") (name "Net-(U3-IN1+)") (class "Default")
      (node (ref "RG3") (pin "2") (pinfunction "2_2") (pintype "passive"))
      (node (ref "U3") (pin "3") (pinfunction "IN1+_3") (pintype "input"))
    )
    (net (code "56") (name "Net-(U3-IN2+)") (class "Default")
      (node (ref "RH3") (pin "2") (pinfunction "2_2") (pintype "passive"))
      (node (ref "U3") (pin "5") (pinfunction "IN2+_5") (pintype "input"))
    )
    (net (code "57") (name "unconnected-(50-1-RST-Pad8)") (class "Default")
      (node (ref "50-1") (pin "8") (pinfunction "RST_8") (pintype "passive"))
    )
    (net (code "58") (name "unconnected-(50-2-RST-Pad8)") (class "Default")
      (node (ref "50-2") (pin "8") (pinfunction "RST_8") (pintype "passive"))
    )
    (net (code "59") (name "unconnected-(7333-RST-Pad8)") (class "Default")
      (node (ref "7333") (pin "8") (pinfunction "RST_8") (pintype "passive"))
    )
    (net (code "60") (name "unconnected-(EC-Pad5)") (class "Default")
      (node (ref "EC") (pin "5") (pinfunction "5_5") (pintype "passive"))
    )
    (net (code "61") (name "unconnected-(EC-Pad6)") (class "Default")
      (node (ref "EC") (pin "6") (pinfunction "6_6") (pintype "passive"))
    )
    (net (code "62") (name "unconnected-(LQ_KXXP144-SYSVG-ADC0_DM1-Pad18)") (class "Default")
      (node (ref "LQ_KXXP144-SYSVG") (pin "18") (pinfunction "ADC0_DM1_18") (pintype "passive"))
    )
    (net (code "63") (name "unconnected-(LQ_KXXP144-SYSVG-ADC0_DM3-Pad24)") (class "Default")
      (node (ref "LQ_KXXP144-SYSVG") (pin "24") (pinfunction "ADC0_DM3_24") (pintype "passive"))
    )
    (net (code "64") (name "unconnected-(LQ_KXXP144-SYSVG-ADC0_DP1-Pad17)") (class "Default")
      (node (ref "LQ_KXXP144-SYSVG") (pin "17") (pinfunction "ADC0_DP1_17") (pintype "passive"))
    )
    (net (code "65") (name "unconnected-(LQ_KXXP144-SYSVG-ADC0_DP3-Pad23)") (class "Default")
      (node (ref "LQ_KXXP144-SYSVG") (pin "23") (pinfunction "ADC0_DP3_23") (pintype "passive"))
    )
    (net (code "66") (name "unconnected-(LQ_KXXP144-SYSVG-ADC0_SE16-Pad27)") (class "Default")
      (node (ref "LQ_KXXP144-SYSVG") (pin "27") (pinfunction "ADC0_SE16_27") (pintype "passive"))
    )
    (net (code "67") (name "unconnected-(LQ_KXXP144-SYSVG-ADC1-DP1-Pad19)") (class "Default")
      (node (ref "LQ_KXXP144-SYSVG") (pin "19") (pinfunction "ADC1-DP1_19") (pintype "passive"))
    )
    (net (code "68") (name "unconnected-(LQ_KXXP144-SYSVG-ADC1_DM1-Pad20)") (class "Default")
      (node (ref "LQ_KXXP144-SYSVG") (pin "20") (pinfunction "ADC1_DM1_20") (pintype "passive"))
    )
    (net (code "69") (name "unconnected-(LQ_KXXP144-SYSVG-ADC1_DM3-Pad22)") (class "Default")
      (node (ref "LQ_KXXP144-SYSVG") (pin "22") (pinfunction "ADC1_DM3_22") (pintype "passive"))
    )
    (net (code "70") (name "unconnected-(LQ_KXXP144-SYSVG-ADC1_DP3-Pad21)") (class "Default")
      (node (ref "LQ_KXXP144-SYSVG") (pin "21") (pinfunction "ADC1_DP3_21") (pintype "passive"))
    )
    (net (code "71") (name "unconnected-(LQ_KXXP144-SYSVG-ADC1_SE16-Pad26)") (class "Default")
      (node (ref "LQ_KXXP144-SYSVG") (pin "26") (pinfunction "ADC1_SE16_26") (pintype "passive"))
    )
    (net (code "72") (name "unconnected-(LQ_KXXP144-SYSVG-ADC1_SE18-Pad28)") (class "Default")
      (node (ref "LQ_KXXP144-SYSVG") (pin "28") (pinfunction "ADC1_SE18_28") (pintype "passive"))
    )
    (net (code "73") (name "unconnected-(LQ_KXXP144-SYSVG-BAT-Pad31)") (class "Default")
      (node (ref "LQ_KXXP144-SYSVG") (pin "31") (pinfunction "BAT_31") (pintype "passive"))
    )
    (net (code "74") (name "unconnected-(LQ_KXXP144-SYSVG-DAC0_OUT-Pad29)") (class "Default")
      (node (ref "LQ_KXXP144-SYSVG") (pin "29") (pinfunction "DAC0_OUT_29") (pintype "passive"))
    )
    (net (code "75") (name "unconnected-(LQ_KXXP144-SYSVG-DAC1_OUT-Pad30)") (class "Default")
      (node (ref "LQ_KXXP144-SYSVG") (pin "30") (pinfunction "DAC1_OUT_30") (pintype "passive"))
    )
    (net (code "76") (name "unconnected-(LQ_KXXP144-SYSVG-NC-Pad37)") (class "Default")
      (node (ref "LQ_KXXP144-SYSVG") (pin "37") (pinfunction "NC_37") (pintype "passive"))
    )
    (net (code "77") (name "unconnected-(LQ_KXXP144-SYSVG-NC-Pad39)") (class "Default")
      (node (ref "LQ_KXXP144-SYSVG") (pin "39") (pinfunction "NC_39") (pintype "passive"))
    )
    (net (code "78") (name "unconnected-(LQ_KXXP144-SYSVG-PTA0-Pad44)") (class "Default")
      (node (ref "LQ_KXXP144-SYSVG") (pin "44") (pinfunction "PTA0_44") (pintype "passive"))
    )
    (net (code "79") (name "unconnected-(LQ_KXXP144-SYSVG-PTA1-Pad40)") (class "Default")
      (node (ref "LQ_KXXP144-SYSVG") (pin "40") (pinfunction "PTA1_40") (pintype "passive"))
    )
    (net (code "80") (name "unconnected-(LQ_KXXP144-SYSVG-PTA2-Pad42)") (class "Default")
      (node (ref "LQ_KXXP144-SYSVG") (pin "42") (pinfunction "PTA2_42") (pintype "passive"))
    )
    (net (code "81") (name "unconnected-(LQ_KXXP144-SYSVG-PTA3-Pad46)") (class "Default")
      (node (ref "LQ_KXXP144-SYSVG") (pin "46") (pinfunction "PTA3_46") (pintype "passive"))
    )
    (net (code "82") (name "unconnected-(LQ_KXXP144-SYSVG-PTA4-Pad47)") (class "Default")
      (node (ref "LQ_KXXP144-SYSVG") (pin "47") (pinfunction "PTA4_47") (pintype "passive"))
    )
    (net (code "83") (name "unconnected-(LQ_KXXP144-SYSVG-PTA5-Pad48)") (class "Default")
      (node (ref "LQ_KXXP144-SYSVG") (pin "48") (pinfunction "PTA5_48") (pintype "passive"))
    )
    (net (code "84") (name "unconnected-(LQ_KXXP144-SYSVG-PTA6-Pad49)") (class "Default")
      (node (ref "LQ_KXXP144-SYSVG") (pin "49") (pinfunction "PTA6_49") (pintype "passive"))
    )
    (net (code "85") (name "unconnected-(LQ_KXXP144-SYSVG-PTA7-Pad50)") (class "Default")
      (node (ref "LQ_KXXP144-SYSVG") (pin "50") (pinfunction "PTA7_50") (pintype "passive"))
    )
    (net (code "86") (name "unconnected-(LQ_KXXP144-SYSVG-PTA8-Pad51)") (class "Default")
      (node (ref "LQ_KXXP144-SYSVG") (pin "51") (pinfunction "PTA8_51") (pintype "passive"))
    )
    (net (code "87") (name "unconnected-(LQ_KXXP144-SYSVG-PTA9-Pad52)") (class "Default")
      (node (ref "LQ_KXXP144-SYSVG") (pin "52") (pinfunction "PTA9_52") (pintype "passive"))
    )
    (net (code "88") (name "unconnected-(LQ_KXXP144-SYSVG-PTA10-Pad53)") (class "Default")
      (node (ref "LQ_KXXP144-SYSVG") (pin "53") (pinfunction "PTA10_53") (pintype "passive"))
    )
    (net (code "89") (name "unconnected-(LQ_KXXP144-SYSVG-PTA11-Pad54)") (class "Default")
      (node (ref "LQ_KXXP144-SYSVG") (pin "54") (pinfunction "PTA11_54") (pintype "passive"))
    )
    (net (code "90") (name "unconnected-(LQ_KXXP144-SYSVG-PTA12-Pad55)") (class "Default")
      (node (ref "LQ_KXXP144-SYSVG") (pin "55") (pinfunction "PTA12_55") (pintype "passive"))
    )
    (net (code "91") (name "unconnected-(LQ_KXXP144-SYSVG-PTA13-Pad56)") (class "Default")
      (node (ref "LQ_KXXP144-SYSVG") (pin "56") (pinfunction "PTA13_56") (pintype "passive"))
    )
    (net (code "92") (name "unconnected-(LQ_KXXP144-SYSVG-PTA14-Pad57)") (class "Default")
      (node (ref "LQ_KXXP144-SYSVG") (pin "57") (pinfunction "PTA14_57") (pintype "passive"))
    )
    (net (code "93") (name "unconnected-(LQ_KXXP144-SYSVG-PTA15-Pad58)") (class "Default")
      (node (ref "LQ_KXXP144-SYSVG") (pin "58") (pinfunction "PTA15_58") (pintype "passive"))
    )
    (net (code "94") (name "unconnected-(LQ_KXXP144-SYSVG-PTA16-Pad59)") (class "Default")
      (node (ref "LQ_KXXP144-SYSVG") (pin "59") (pinfunction "PTA16_59") (pintype "passive"))
    )
    (net (code "95") (name "unconnected-(LQ_KXXP144-SYSVG-PTA17-Pad60)") (class "Default")
      (node (ref "LQ_KXXP144-SYSVG") (pin "60") (pinfunction "PTA17_60") (pintype "passive"))
    )
    (net (code "96") (name "unconnected-(LQ_KXXP144-SYSVG-PTA18-Pad61)") (class "Default")
      (node (ref "LQ_KXXP144-SYSVG") (pin "61") (pinfunction "PTA18_61") (pintype "passive"))
    )
    (net (code "97") (name "unconnected-(LQ_KXXP144-SYSVG-PTA19-Pad62)") (class "Default")
      (node (ref "LQ_KXXP144-SYSVG") (pin "62") (pinfunction "PTA19_62") (pintype "passive"))
    )
    (net (code "98") (name "unconnected-(LQ_KXXP144-SYSVG-PTA24-Pad64)") (class "Default")
      (node (ref "LQ_KXXP144-SYSVG") (pin "64") (pinfunction "PTA24_64") (pintype "passive"))
    )
    (net (code "99") (name "unconnected-(LQ_KXXP144-SYSVG-PTA25-Pad63)") (class "Default")
      (node (ref "LQ_KXXP144-SYSVG") (pin "63") (pinfunction "PTA25_63") (pintype "passive"))
    )
    (net (code "100") (name "unconnected-(LQ_KXXP144-SYSVG-PTA26-Pad66)") (class "Default")
      (node (ref "LQ_KXXP144-SYSVG") (pin "66") (pinfunction "PTA26_66") (pintype "passive"))
    )
    (net (code "101") (name "unconnected-(LQ_KXXP144-SYSVG-PTA27-Pad65)") (class "Default")
      (node (ref "LQ_KXXP144-SYSVG") (pin "65") (pinfunction "PTA27_65") (pintype "passive"))
    )
    (net (code "102") (name "unconnected-(LQ_KXXP144-SYSVG-PTA28-Pad68)") (class "Default")
      (node (ref "LQ_KXXP144-SYSVG") (pin "68") (pinfunction "PTA28_68") (pintype "passive"))
    )
    (net (code "103") (name "unconnected-(LQ_KXXP144-SYSVG-PTA29-Pad67)") (class "Default")
      (node (ref "LQ_KXXP144-SYSVG") (pin "67") (pinfunction "PTA29_67") (pintype "passive"))
    )
    (net (code "104") (name "unconnected-(LQ_KXXP144-SYSVG-PTB0-Pad70)") (class "Default")
      (node (ref "LQ_KXXP144-SYSVG") (pin "70") (pinfunction "PTB0_70") (pintype "passive"))
    )
    (net (code "105") (name "unconnected-(LQ_KXXP144-SYSVG-PTB1-Pad69)") (class "Default")
      (node (ref "LQ_KXXP144-SYSVG") (pin "69") (pinfunction "PTB1_69") (pintype "passive"))
    )
    (net (code "106") (name "unconnected-(LQ_KXXP144-SYSVG-PTB2-Pad72)") (class "Default")
      (node (ref "LQ_KXXP144-SYSVG") (pin "72") (pinfunction "PTB2_72") (pintype "passive"))
    )
    (net (code "107") (name "unconnected-(LQ_KXXP144-SYSVG-PTB3-Pad71)") (class "Default")
      (node (ref "LQ_KXXP144-SYSVG") (pin "71") (pinfunction "PTB3_71") (pintype "passive"))
    )
    (net (code "108") (name "unconnected-(LQ_KXXP144-SYSVG-PTB8-Pad78)") (class "Default")
      (node (ref "LQ_KXXP144-SYSVG") (pin "78") (pinfunction "PTB8_78") (pintype "passive"))
    )
    (net (code "109") (name "unconnected-(LQ_KXXP144-SYSVG-PTB9-Pad77)") (class "Default")
      (node (ref "LQ_KXXP144-SYSVG") (pin "77") (pinfunction "PTB9_77") (pintype "passive"))
    )
    (net (code "110") (name "unconnected-(LQ_KXXP144-SYSVG-PTB16-Pad82)") (class "Default")
      (node (ref "LQ_KXXP144-SYSVG") (pin "82") (pinfunction "PTB16_82") (pintype "passive"))
    )
    (net (code "111") (name "unconnected-(LQ_KXXP144-SYSVG-PTB17-Pad81)") (class "Default")
      (node (ref "LQ_KXXP144-SYSVG") (pin "81") (pinfunction "PTB17_81") (pintype "passive"))
    )
    (net (code "112") (name "unconnected-(LQ_KXXP144-SYSVG-PTB20-Pad86)") (class "Default")
      (node (ref "LQ_KXXP144-SYSVG") (pin "86") (pinfunction "PTB20_86") (pintype "passive"))
    )
    (net (code "113") (name "unconnected-(LQ_KXXP144-SYSVG-PTB21-Pad85)") (class "Default")
      (node (ref "LQ_KXXP144-SYSVG") (pin "85") (pinfunction "PTB21_85") (pintype "passive"))
    )
    (net (code "114") (name "unconnected-(LQ_KXXP144-SYSVG-PTB22-Pad88)") (class "Default")
      (node (ref "LQ_KXXP144-SYSVG") (pin "88") (pinfunction "PTB22_88") (pintype "passive"))
    )
    (net (code "115") (name "unconnected-(LQ_KXXP144-SYSVG-PTB23-Pad87)") (class "Default")
      (node (ref "LQ_KXXP144-SYSVG") (pin "87") (pinfunction "PTB23_87") (pintype "passive"))
    )
    (net (code "116") (name "unconnected-(LQ_KXXP144-SYSVG-PTC0-Pad90)") (class "Default")
      (node (ref "LQ_KXXP144-SYSVG") (pin "90") (pinfunction "PTC0_90") (pintype "passive"))
    )
    (net (code "117") (name "unconnected-(LQ_KXXP144-SYSVG-PTC3-Pad91)") (class "Default")
      (node (ref "LQ_KXXP144-SYSVG") (pin "91") (pinfunction "PTC3_91") (pintype "passive"))
    )
    (net (code "118") (name "unconnected-(LQ_KXXP144-SYSVG-PTC6-Pad96)") (class "Default")
      (node (ref "LQ_KXXP144-SYSVG") (pin "96") (pinfunction "PTC6_96") (pintype "passive"))
    )
    (net (code "119") (name "unconnected-(LQ_KXXP144-SYSVG-PTC7-Pad95)") (class "Default")
      (node (ref "LQ_KXXP144-SYSVG") (pin "95") (pinfunction "PTC7_95") (pintype "passive"))
    )
    (net (code "120") (name "unconnected-(LQ_KXXP144-SYSVG-PTC8-Pad98)") (class "Default")
      (node (ref "LQ_KXXP144-SYSVG") (pin "98") (pinfunction "PTC8_98") (pintype "passive"))
    )
    (net (code "121") (name "unconnected-(LQ_KXXP144-SYSVG-PTC9-Pad97)") (class "Default")
      (node (ref "LQ_KXXP144-SYSVG") (pin "97") (pinfunction "PTC9_97") (pintype "passive"))
    )
    (net (code "122") (name "unconnected-(LQ_KXXP144-SYSVG-PTC11-Pad99)") (class "Default")
      (node (ref "LQ_KXXP144-SYSVG") (pin "99") (pinfunction "PTC11_99") (pintype "passive"))
    )
    (net (code "123") (name "unconnected-(LQ_KXXP144-SYSVG-PTC12-Pad102)") (class "Default")
      (node (ref "LQ_KXXP144-SYSVG") (pin "102") (pinfunction "PTC12_102") (pintype "passive"))
    )
    (net (code "124") (name "unconnected-(LQ_KXXP144-SYSVG-PTC13-Pad101)") (class "Default")
      (node (ref "LQ_KXXP144-SYSVG") (pin "101") (pinfunction "PTC13_101") (pintype "passive"))
    )
    (net (code "125") (name "unconnected-(LQ_KXXP144-SYSVG-PTC14-Pad104)") (class "Default")
      (node (ref "LQ_KXXP144-SYSVG") (pin "104") (pinfunction "PTC14_104") (pintype "passive"))
    )
    (net (code "126") (name "unconnected-(LQ_KXXP144-SYSVG-PTC15-Pad103)") (class "Default")
      (node (ref "LQ_KXXP144-SYSVG") (pin "103") (pinfunction "PTC15_103") (pintype "passive"))
    )
    (net (code "127") (name "unconnected-(LQ_KXXP144-SYSVG-PTC16-Pad106)") (class "Default")
      (node (ref "LQ_KXXP144-SYSVG") (pin "106") (pinfunction "PTC16_106") (pintype "passive"))
    )
    (net (code "128") (name "unconnected-(LQ_KXXP144-SYSVG-PTC17-Pad105)") (class "Default")
      (node (ref "LQ_KXXP144-SYSVG") (pin "105") (pinfunction "PTC17_105") (pintype "passive"))
    )
    (net (code "129") (name "unconnected-(LQ_KXXP144-SYSVG-PTC18-Pad108)") (class "Default")
      (node (ref "LQ_KXXP144-SYSVG") (pin "108") (pinfunction "PTC18_108") (pintype "passive"))
    )
    (net (code "130") (name "unconnected-(LQ_KXXP144-SYSVG-PTC19-Pad107)") (class "Default")
      (node (ref "LQ_KXXP144-SYSVG") (pin "107") (pinfunction "PTC19_107") (pintype "passive"))
    )
    (net (code "131") (name "unconnected-(LQ_KXXP144-SYSVG-PTD0-Pad110)") (class "Default")
      (node (ref "LQ_KXXP144-SYSVG") (pin "110") (pinfunction "PTD0_110") (pintype "passive"))
    )
    (net (code "132") (name "unconnected-(LQ_KXXP144-SYSVG-PTD1-Pad109)") (class "Default")
      (node (ref "LQ_KXXP144-SYSVG") (pin "109") (pinfunction "PTD1_109") (pintype "passive"))
    )
    (net (code "133") (name "unconnected-(LQ_KXXP144-SYSVG-PTD2-Pad112)") (class "Default")
      (node (ref "LQ_KXXP144-SYSVG") (pin "112") (pinfunction "PTD2_112") (pintype "passive"))
    )
    (net (code "134") (name "unconnected-(LQ_KXXP144-SYSVG-PTD3-Pad111)") (class "Default")
      (node (ref "LQ_KXXP144-SYSVG") (pin "111") (pinfunction "PTD3_111") (pintype "passive"))
    )
    (net (code "135") (name "unconnected-(LQ_KXXP144-SYSVG-PTD4-Pad114)") (class "Default")
      (node (ref "LQ_KXXP144-SYSVG") (pin "114") (pinfunction "PTD4_114") (pintype "passive"))
    )
    (net (code "136") (name "unconnected-(LQ_KXXP144-SYSVG-PTD5-Pad113)") (class "Default")
      (node (ref "LQ_KXXP144-SYSVG") (pin "113") (pinfunction "PTD5_113") (pintype "passive"))
    )
    (net (code "137") (name "unconnected-(LQ_KXXP144-SYSVG-PTD6-Pad116)") (class "Default")
      (node (ref "LQ_KXXP144-SYSVG") (pin "116") (pinfunction "PTD6_116") (pintype "passive"))
    )
    (net (code "138") (name "unconnected-(LQ_KXXP144-SYSVG-PTD7-Pad115)") (class "Default")
      (node (ref "LQ_KXXP144-SYSVG") (pin "115") (pinfunction "PTD7_115") (pintype "passive"))
    )
    (net (code "139") (name "unconnected-(LQ_KXXP144-SYSVG-PTD8-Pad118)") (class "Default")
      (node (ref "LQ_KXXP144-SYSVG") (pin "118") (pinfunction "PTD8_118") (pintype "passive"))
    )
    (net (code "140") (name "unconnected-(LQ_KXXP144-SYSVG-PTD9-Pad117)") (class "Default")
      (node (ref "LQ_KXXP144-SYSVG") (pin "117") (pinfunction "PTD9_117") (pintype "passive"))
    )
    (net (code "141") (name "unconnected-(LQ_KXXP144-SYSVG-PTD11-Pad119)") (class "Default")
      (node (ref "LQ_KXXP144-SYSVG") (pin "119") (pinfunction "PTD11_119") (pintype "passive"))
    )
    (net (code "142") (name "unconnected-(LQ_KXXP144-SYSVG-PTD12-Pad122)") (class "Default")
      (node (ref "LQ_KXXP144-SYSVG") (pin "122") (pinfunction "PTD12_122") (pintype "passive"))
    )
    (net (code "143") (name "unconnected-(LQ_KXXP144-SYSVG-PTD13-Pad121)") (class "Default")
      (node (ref "LQ_KXXP144-SYSVG") (pin "121") (pinfunction "PTD13_121") (pintype "passive"))
    )
    (net (code "144") (name "unconnected-(LQ_KXXP144-SYSVG-PTD14-Pad124)") (class "Default")
      (node (ref "LQ_KXXP144-SYSVG") (pin "124") (pinfunction "PTD14_124") (pintype "passive"))
    )
    (net (code "145") (name "unconnected-(LQ_KXXP144-SYSVG-PTD15-Pad123)") (class "Default")
      (node (ref "LQ_KXXP144-SYSVG") (pin "123") (pinfunction "PTD15_123") (pintype "passive"))
    )
    (net (code "146") (name "unconnected-(LQ_KXXP144-SYSVG-PTE0-Pad1)") (class "Default")
      (node (ref "LQ_KXXP144-SYSVG") (pin "1") (pinfunction "PTE0_1") (pintype "passive"))
    )
    (net (code "147") (name "unconnected-(LQ_KXXP144-SYSVG-PTE1-Pad2)") (class "Default")
      (node (ref "LQ_KXXP144-SYSVG") (pin "2") (pinfunction "PTE1_2") (pintype "passive"))
    )
    (net (code "148") (name "unconnected-(LQ_KXXP144-SYSVG-PTE5-Pad6)") (class "Default")
      (node (ref "LQ_KXXP144-SYSVG") (pin "6") (pinfunction "PTE5_6") (pintype "passive"))
    )
    (net (code "149") (name "unconnected-(LQ_KXXP144-SYSVG-PTE10-Pad11)") (class "Default")
      (node (ref "LQ_KXXP144-SYSVG") (pin "11") (pinfunction "PTE10_11") (pintype "passive"))
    )
    (net (code "150") (name "unconnected-(LQ_KXXP144-SYSVG-PTE11-Pad12)") (class "Default")
      (node (ref "LQ_KXXP144-SYSVG") (pin "12") (pinfunction "PTE11_12") (pintype "passive"))
    )
    (net (code "151") (name "unconnected-(LQ_KXXP144-SYSVG-PTE12-Pad13)") (class "Default")
      (node (ref "LQ_KXXP144-SYSVG") (pin "13") (pinfunction "PTE12_13") (pintype "passive"))
    )
    (net (code "152") (name "unconnected-(LQ_KXXP144-SYSVG-PTE24-Pad32)") (class "Default")
      (node (ref "LQ_KXXP144-SYSVG") (pin "32") (pinfunction "PTE24_32") (pintype "passive"))
    )
    (net (code "153") (name "unconnected-(LQ_KXXP144-SYSVG-PTE25-Pad33)") (class "Default")
      (node (ref "LQ_KXXP144-SYSVG") (pin "33") (pinfunction "PTE25_33") (pintype "passive"))
    )
    (net (code "154") (name "unconnected-(LQ_KXXP144-SYSVG-PTE26-Pad34)") (class "Default")
      (node (ref "LQ_KXXP144-SYSVG") (pin "34") (pinfunction "PTE26_34") (pintype "passive"))
    )
    (net (code "155") (name "unconnected-(LQ_KXXP144-SYSVG-PTE27-Pad35)") (class "Default")
      (node (ref "LQ_KXXP144-SYSVG") (pin "35") (pinfunction "PTE27_35") (pintype "passive"))
    )
    (net (code "156") (name "unconnected-(LQ_KXXP144-SYSVG-PTE28-Pad36)") (class "Default")
      (node (ref "LQ_KXXP144-SYSVG") (pin "36") (pinfunction "PTE28_36") (pintype "passive"))
    )
    (net (code "157") (name "unconnected-(LQ_KXXP144-SYSVG-RESET-Pad38)") (class "Default")
      (node (ref "LQ_KXXP144-SYSVG") (pin "38") (pinfunction "RESET_38") (pintype "passive"))
    )
    (net (code "158") (name "unconnected-(LQ_KXXP144-SYSVG-USB0_DM-Pad15)") (class "Default")
      (node (ref "LQ_KXXP144-SYSVG") (pin "15") (pinfunction "USB0_DM_15") (pintype "passive"))
    )
    (net (code "159") (name "unconnected-(LQ_KXXP144-SYSVG-USB0_DP-Pad14)") (class "Default")
      (node (ref "LQ_KXXP144-SYSVG") (pin "14") (pinfunction "USB0_DP_14") (pintype "passive"))
    )
    (net (code "160") (name "unconnected-(LQ_KXXP144-SYSVG-VREFH-Pad25)") (class "Default")
      (node (ref "LQ_KXXP144-SYSVG") (pin "25") (pinfunction "VREFH_25") (pintype "passive"))
    )
    (net (code "161") (name "unconnected-(LQ_KXXP144-SYSVG-VREGIN-Pad16)") (class "Default")
      (node (ref "LQ_KXXP144-SYSVG") (pin "16") (pinfunction "VREGIN_16") (pintype "passive"))
    )
  )
)
